# SOP8_flash.net
KiCad netlist of a schematic drawn in Altium Designer
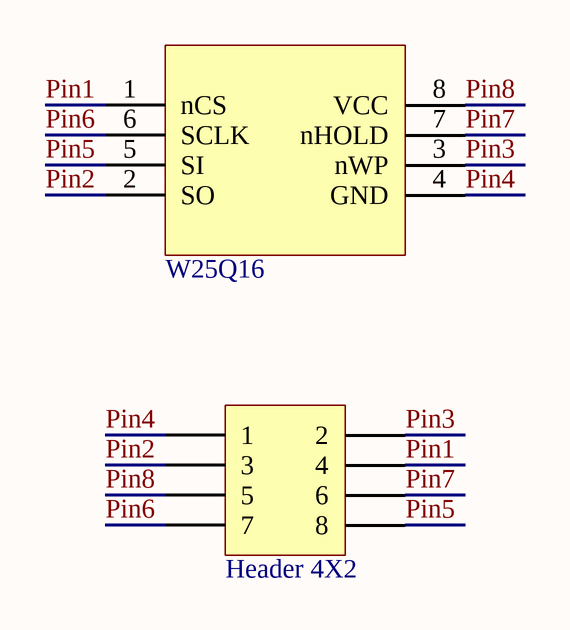
[diagram p0: SOP8 flash转接板.SchDoc]

(export (version "E")
  (design (tool "Eeschema 10.0.6"))
  (components
    (comp (ref "P1")
      (value "Header 4X2")
      (footprint "CN_4X2P_1.27MM")
      (description "Header, 4-Pin, Dual row")
      (fields (field (name "PUBLISHER") "Altium Limited"))
      (libsource (lib "Miscellaneous Connectors") (part "Header 4X2"))
    )
    (comp (ref "U1") (value "W25Q16") (footprint "SOIC8-50X204") (libsource (lib "Gsd") (part "MX25Lxx")))
  )
  (nets
    (net (code "1") (name "/Pin1") (class "Default")
      (node (ref "P1") (pin "4") (pinfunction "4_4") (pintype "passive"))
      (node (ref "U1") (pin "1") (pinfunction "nCS_1") (pintype "passive"))
    )
    (net (code "2") (name "/Pin2") (class "Default")
      (node (ref "P1") (pin "3") (pinfunction "3_3") (pintype "passive"))
      (node (ref "U1") (pin "2") (pinfunction "SO_2") (pintype "passive"))
    )
    (net (code "3") (name "/Pin3") (class "Default")
      (node (ref "P1") (pin "2") (pinfunction "2_2") (pintype "passive"))
      (node (ref "U1") (pin "3") (pinfunction "nWP_3") (pintype "passive"))
    )
    (net (code "4") (name "/Pin4") (class "Default")
      (node (ref "P1") (pin "1") (pinfunction "1_1") (pintype "passive"))
      (node (ref "U1") (pin "4") (pinfunction "GND_4") (pintype "passive"))
    )
    (net (code "5") (name "/Pin5") (class "Default")
      (node (ref "P1") (pin "8") (pinfunction "8_8") (pintype "passive"))
      (node (ref "U1") (pin "5") (pinfunction "SI_5") (pintype "passive"))
    )
    (net (code "6") (name "/Pin6") (class "Default")
      (node (ref "P1") (pin "7") (pinfunction "7_7") (pintype "passive"))
      (node (ref "U1") (pin "6") (pinfunction "SCLK_6") (pintype "passive"))
    )
    (net (code "7") (name "/Pin7") (class "Default")
      (node (ref "P1") (pin "6") (pinfunction "6_6") (pintype "passive"))
      (node (ref "U1") (pin "7") (pinfunction "nHOLD_7") (pintype "passive"))
    )
    (net (code "8") (name "/Pin8") (class "Default")
      (node (ref "P1") (pin "5") (pinfunction "5_5") (pintype "passive"))
      (node (ref "U1") (pin "8") (pinfunction "VCC_8") (pintype "passive"))
    )
  )
)
